# MP_Power_Circuit.net
KiCad netlist of a schematic drawn in Altium Designer
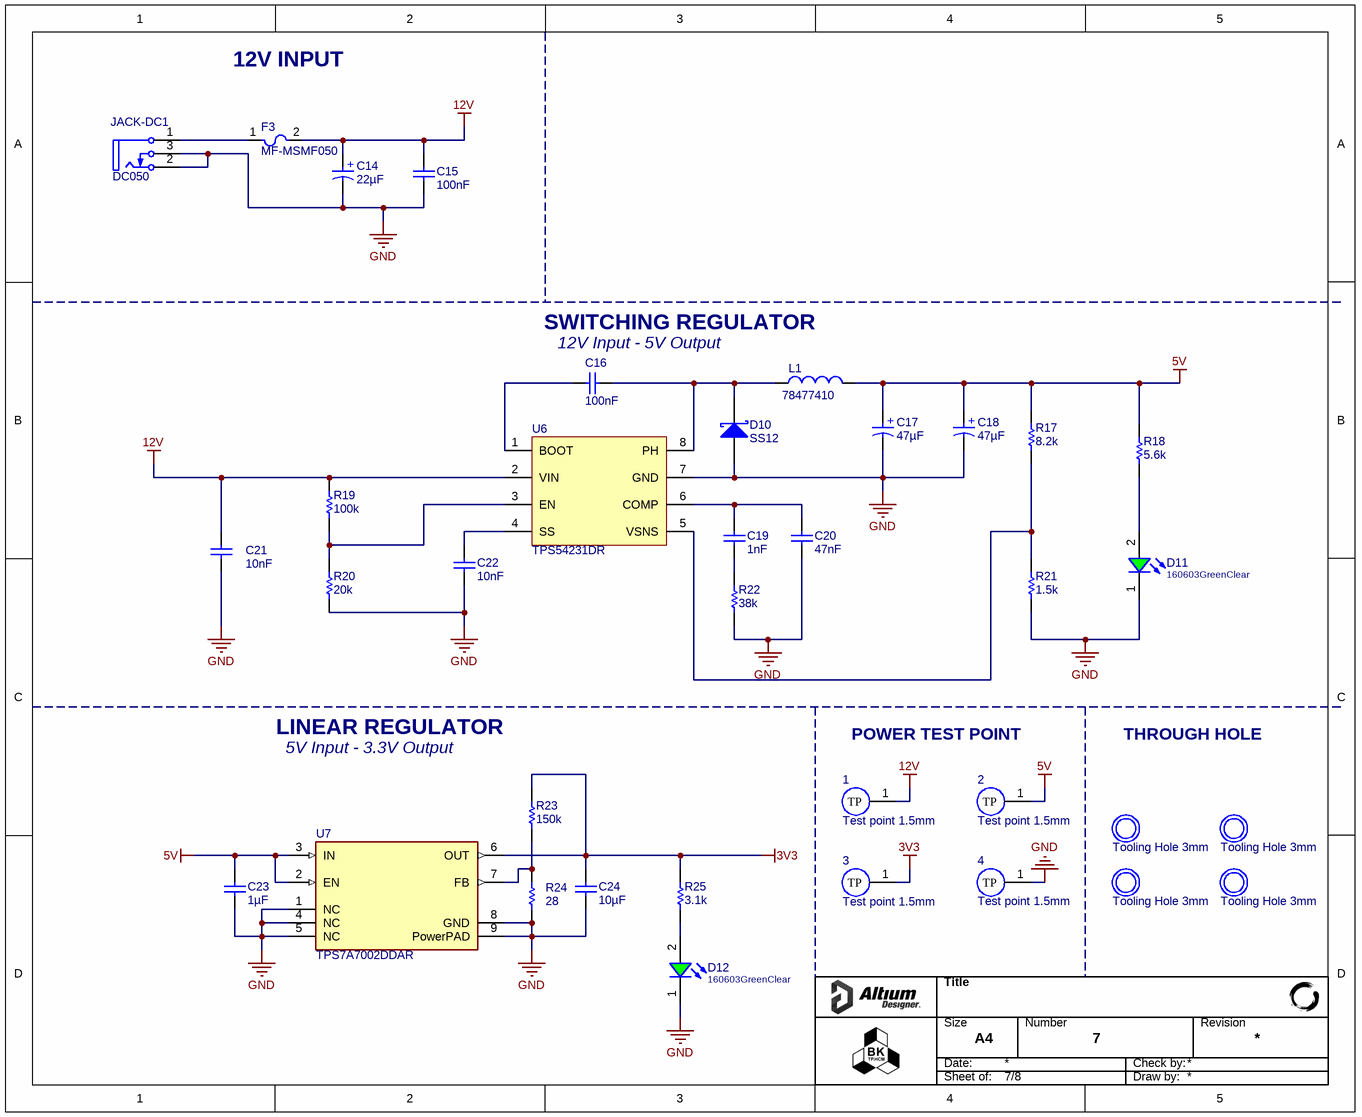
[diagram p0: [MP] Power Circuit.SchDoc]

(export (version "E")
  (design (tool "Eeschema 10.0.6"))
  (components
    (comp (ref "1")
      (value "Test point 1.5mm")
      (footprint "Test point 1.5mm-Footprint-1")
      (description "Test point, 1.5mm radius")
      (libsource (lib "University of Technology") (part "TP"))
    )
    (comp (ref "2")
      (value "Test point 1.5mm")
      (footprint "Test point 1.5mm-Footprint-1")
      (description "Test point, 1.5mm radius")
      (libsource (lib "University of Technology") (part "TP"))
    )
    (comp (ref "3")
      (value "Test point 1.5mm")
      (footprint "Test point 1.5mm-Footprint-1")
      (description "Test point, 1.5mm radius")
      (libsource (lib "University of Technology") (part "TP"))
    )
    (comp (ref "4")
      (value "Test point 1.5mm")
      (footprint "Test point 1.5mm-Footprint-1")
      (description "Test point, 1.5mm radius")
      (libsource (lib "University of Technology") (part "TP"))
    )
    (comp (ref "C14")
      (value "22µF")
      (footprint "WCAP-ASLI_D4H5.5")
      (description "V-Chip, D4 x H5.5mm, 22uF, 16V")
      (fields (field (name "MANUFACTURER") "Wurth Elektronik") (field (name "Comment") "865080340003"))
      (libsource (lib "University of Technology") (part "0710101508650801570160U20"))
    )
    (comp (ref "C15")
      (value "100nF")
      (footprint "CAP_0603")
      (description "CAP, size 0603, 100 nF, 50 VDC, 10%")
      (fields
        (field (name "TOLERANCE") "10%")
        (field (name "MANUFACTURER PART NUMBER") "CGA3E3X8R1H104K080AE")
        (field (name "SOURCE") "Capacitor_0603_10_percent.SchLib")
      )
      (libsource (lib "University of Technology") (part "010603475106.3"))
    )
    (comp (ref "C16")
      (value "100nF")
      (footprint "CAP_0603")
      (description "CAP, size 0603, 100 nF, 50 VDC, 10%")
      (fields
        (field (name "TOLERANCE") "10%")
        (field (name "MANUFACTURER PART NUMBER") "CGA3E3X8R1H104K080AE")
        (field (name "SOURCE") "Capacitor_0603_10_percent.SchLib")
      )
      (libsource (lib "University of Technology") (part "010603475106.3"))
    )
    (comp (ref "C17")
      (value "47µF")
      (footprint "WCAP-ASLI_D5H5.5")
      (description "V-Chip, D5 x H5.5mm, 47uF, 16V")
      (fields (field (name "MANUFACTURER") "Wurth Elektronik") (field (name "Comment") "865080342006"))
      (libsource (lib "University of Technology") (part "0710101508650801570160U20"))
    )
    (comp (ref "C18")
      (value "47µF")
      (footprint "WCAP-ASLI_D5H5.5")
      (description "V-Chip, D5 x H5.5mm, 47uF, 16V")
      (fields (field (name "MANUFACTURER") "Wurth Elektronik") (field (name "Comment") "865080342006"))
      (libsource (lib "University of Technology") (part "0710101508650801570160U20"))
    )
    (comp (ref "C19")
      (value "1nF")
      (footprint "CAP_0603")
      (description "CAP, size 0603, 1 nF, 50 VDC, 5%")
      (fields
        (field (name "MANUFACTURER") "TDK")
        (field (name "MANUFACTURER PART NUMBER") "CGA3E2NP01H102J080AA")
        (field (name "SOURCE") "Capacitor_0603_5_percent.SchLib")
      )
      (libsource (lib "University of Technology") (part "0106036820550"))
    )
    (comp (ref "C20")
      (value "47nF")
      (footprint "CAP_0603")
      (description "CAP, size 0603, 47 nF, 50 VDC, 10%")
      (fields
        (field (name "MANUFACTURER PART NUMBER") "CGA3E2X7R1H473K080AA")
        (field (name "MANUFACTURER") "TDK")
        (field (name "SOURCE") "Capacitor_0603_10_percent.SchLib")
      )
      (libsource (lib "University of Technology") (part "010603475106.3"))
    )
    (comp (ref "C21")
      (value "10nF")
      (footprint "CAP_0603")
      (description "CAP, size 0603, 10 nF, 50 VDC, 5%")
      (fields
        (field (name "TOLERANCE") "5%")
        (field (name "MANUFACTURER") "TDK")
        (field (name "SOURCE") "Capacitor_0603_5_percent.SchLib")
      )
      (libsource (lib "University of Technology") (part "0106036820550"))
    )
    (comp (ref "C22")
      (value "10nF")
      (footprint "CAP_0603")
      (description "CAP, size 0603, 10 nF, 50 VDC, 5%")
      (fields
        (field (name "TOLERANCE") "5%")
        (field (name "MANUFACTURER") "TDK")
        (field (name "SOURCE") "Capacitor_0603_5_percent.SchLib")
      )
      (libsource (lib "University of Technology") (part "0106036820550"))
    )
    (comp (ref "C23")
      (value "1µF")
      (footprint "CAP_0603")
      (description "CAP, size 0603, 1 uF, 25 VDC, 10%")
      (fields
        (field (name "MANUFACTURER") "Samsung Electro-Mechanics")
        (field (name "MANUFACTURER PART NUMBER") "CL10A105KA8NNNC")
        (field (name "SOURCE") "Capacitor_0603_10_percent.SchLib")
      )
      (libsource (lib "University of Technology") (part "010603475106.3"))
    )
    (comp (ref "C24")
      (value "10µF")
      (footprint "CAP_0603")
      (description "CAP, size 0603, 10 uF, 10 VDC, 10%")
      (fields
        (field (name "MANUFACTURER") "Samsung Electro-Mechanics")
        (field (name "LCSC PART #") "C19702")
        (field (name "SOURCE") "Capacitor_0603_10_percent.SchLib")
      )
      (libsource (lib "University of Technology") (part "010603475106.3"))
    )
    (comp (ref "D10")
      (value "SS12")
      (footprint "FAIR-DO-214AC-2_V")
      (description "Schottky Rectifier, 20 V, 1 A, -65 to 125 degC, 2-Pin DO-214AC, RoHS, Tape and Reel")
      (fields (field (name "MANUFACTURER") "Fairchild"))
      (libsource (lib "University of Technology") (part "DSKY-AK-2"))
    )
    (comp (ref "D11")
      (value "160603GreenClear")
      (footprint "WL-SMCW_0603_H=0.7mm")
      (description "WL-SMCW SMT Mono-color Chip LED Waterclear, size 0603, Green, 3.2V, 140deg")
      (libsource (lib "University of Technology") (part "160603GreenClear"))
    )
    (comp (ref "D12")
      (value "160603GreenClear")
      (footprint "WL-SMCW_0603_H=0.7mm")
      (description "WL-SMCW SMT Mono-color Chip LED Waterclear, size 0603, Green, 3.2V, 140deg")
      (libsource (lib "University of Technology") (part "160603GreenClear"))
    )
    (comp (ref "F3")
      (value "MF-MSMF050")
      (footprint "BOUR-MF-MSMF050-2_V")
      (description "PTC Resettable Fuse, 15 V, 500 mA, -40 to 85 degC, 2-Pin SMD, RoHS, Tape and Reel")
      (fields (field (name "MANUFACTURER") "Bourns"))
      (libsource (lib "University of Technology") (part "FUSE-2"))
    )
    (comp (ref "H1")
      (value "Tooling Hole 3mm")
      (footprint "3mm")
      (libsource (lib "University of Technology") (part "Tooling Hole 5mm"))
    )
    (comp (ref "H2")
      (value "Tooling Hole 3mm")
      (footprint "3mm")
      (libsource (lib "University of Technology") (part "Tooling Hole 5mm"))
    )
    (comp (ref "H3")
      (value "Tooling Hole 3mm")
      (footprint "3mm")
      (libsource (lib "University of Technology") (part "Tooling Hole 5mm"))
    )
    (comp (ref "H4")
      (value "Tooling Hole 3mm")
      (footprint "3mm")
      (libsource (lib "University of Technology") (part "Tooling Hole 5mm"))
    )
    (comp (ref "JACK-DC1")
      (value "DC050")
      (footprint "DC050-Footprint-1")
      (description "DinxDout 2.1mm-55mm Jack Power DC Receptacle")
      (libsource (lib "University of Technology") (part "J?"))
    )
    (comp (ref "L1")
      (value "78477410")
      (footprint "WE-PD2A_5848")
      (description "General Purpose Inductor")
      (libsource (lib "University of Technology") (part "IND-2_1"))
    )
    (comp (ref "R17")
      (value "8.2k")
      (footprint "0006038251")
      (description "RES, size 0603, 8.2 KOhm, 1/10 W, 1%")
      (fields (field (name "Comment") "0006038251"))
      (libsource (lib "University of Technology") (part "0006038251"))
    )
    (comp (ref "R18")
      (value "5.6k")
      (footprint "RES_0603")
      (description "RES, size 0603, 5.6 KOhm, 1/10 W, 1%")
      (fields (field (name "MANUFACTURER PART NUMBER") "OEM") (field (name "TOLERANCE") "1%"))
      (libsource (lib "University of Technology") (part "00060371541"))
    )
    (comp (ref "R19")
      (value "100k")
      (footprint "RES_0603")
      (description "RES, size 0603, 100 KOhm, 1/10 W, 1%")
      (fields (field (name "MANUFACTURER PART NUMBER") "OEM") (field (name "TOLERANCE") "1%"))
      (libsource (lib "University of Technology") (part "00060371541"))
    )
    (comp (ref "R20")
      (value "20k")
      (footprint "RES_0603")
      (description "RES, size 0603, 20 KOhm, 1/10 W, 1%")
      (fields (field (name "TOLERANCE") "1%") (field (name "LCSC PART #") "C105575"))
      (libsource (lib "University of Technology") (part "00060371541"))
    )
    (comp (ref "R21")
      (value "1.5k")
      (footprint "RES_0603")
      (description "RES, size 0603, 1.5 KOhm, 1/10 W, 1%")
      (fields (field (name "TOLERANCE") "1%") (field (name "MANUFACTURER") "OEM"))
      (libsource (lib "University of Technology") (part "00060371541"))
    )
    (comp (ref "R22")
      (value "38k")
      (footprint "RES_0603")
      (description "RES, size 0603, 38 KOhm, 1/10 W, 5%")
      (fields (field (name "MANUFACTURER") "OEM") (field (name "TOLERANCE") "5%"))
      (libsource (lib "University of Technology") (part "00060371541"))
    )
    (comp (ref "R23")
      (value "150k")
      (footprint "RES_0603")
      (description "RES, size 0603, 150 KOhm, 1/10 W, 1%")
      (fields (field (name "TOLERANCE") "1%") (field (name "MANUFACTURER PART NUMBER") "OEM"))
      (libsource (lib "University of Technology") (part "00060371541"))
    )
    (comp (ref "R24")
      (value "28")
      (footprint "RES_0603")
      (description "RES, size 0603, 28 Ohm, 1/10 W, 1%")
      (fields (field (name "MANUFACTURER") "OEM") (field (name "TOLERANCE") "1%"))
      (libsource (lib "University of Technology") (part "00060371541"))
    )
    (comp (ref "R25")
      (value "3.1k")
      (footprint "RES_0603")
      (description "RES, size 0603, 3.1  KOhm, 1/10 W, 1%")
      (fields (field (name "MANUFACTURER") "OEM") (field (name "TOLERANCE") "1%"))
      (libsource (lib "University of Technology") (part "00060371541"))
    )
    (comp (ref "U6")
      (value "TPS54231DR")
      (footprint "D0008A_L")
      (description "Switching Regulator, Current-mode, 2A, 570kHz Switching Freq-Max, PDSO8")
      (libsource (lib "University of Technology") (part "TI-TPS54231D8"))
    )
    (comp (ref "U7")
      (value "TPS7A7002DDAR")
      (footprint "FP-DDA0008E-IPC_A")
      (description "Adjustable Positive LDO Regulator, 0.5V Min, 5V Max, 0.6V Dropout, CMOS, PDSO8")
      (libsource (lib "University of Technology") (part "faebeb2d6e46d862d344f00b777028a"))
    )
  )
  (nets
    (net (code "1") (name "3V3") (class "Default")
      (node (ref "3") (pin "1") (pinfunction "TP_1") (pintype "passive"))
      (node (ref "C24") (pin "2") (pinfunction "2_2") (pintype "passive"))
      (node (ref "R23") (pin "2") (pinfunction "2_2") (pintype "passive"))
      (node (ref "R25") (pin "2") (pinfunction "2_2") (pintype "passive"))
      (node (ref "U7") (pin "6") (pinfunction "OUT_6") (pintype "output"))
    )
    (net (code "2") (name "5V") (class "Default")
      (node (ref "2") (pin "1") (pinfunction "TP_1") (pintype "passive"))
      (node (ref "C17") (pin "1") (pinfunction "P_1") (pintype "passive"))
      (node (ref "C18") (pin "1") (pinfunction "P_1") (pintype "passive"))
      (node (ref "C23") (pin "2") (pinfunction "2_2") (pintype "passive"))
      (node (ref "L1") (pin "2") (pinfunction "2_2") (pintype "passive"))
      (node (ref "R17") (pin "2") (pinfunction "2_2") (pintype "passive"))
      (node (ref "R18") (pin "2") (pinfunction "2_2") (pintype "passive"))
      (node (ref "U7") (pin "2") (pinfunction "EN_2") (pintype "input"))
      (node (ref "U7") (pin "3") (pinfunction "IN_3") (pintype "input"))
    )
    (net (code "3") (name "12V") (class "Default")
      (node (ref "1") (pin "1") (pinfunction "TP_1") (pintype "passive"))
      (node (ref "C14") (pin "1") (pinfunction "P_1") (pintype "passive"))
      (node (ref "C15") (pin "1") (pinfunction "1_1") (pintype "passive"))
      (node (ref "C21") (pin "2") (pinfunction "2_2") (pintype "passive"))
      (node (ref "F3") (pin "2") (pinfunction "2_2") (pintype "passive"))
      (node (ref "R19") (pin "2") (pinfunction "2_2") (pintype "passive"))
      (node (ref "U6") (pin "2") (pinfunction "VIN_2") (pintype "passive"))
    )
    (net (code "4") (name "GND") (class "Default")
      (node (ref "4") (pin "1") (pinfunction "TP_1") (pintype "passive"))
      (node (ref "C14") (pin "2") (pinfunction "N_2") (pintype "passive"))
      (node (ref "C15") (pin "2") (pinfunction "2_2") (pintype "passive"))
      (node (ref "C17") (pin "2") (pinfunction "N_2") (pintype "passive"))
      (node (ref "C18") (pin "2") (pinfunction "N_2") (pintype "passive"))
      (node (ref "C20") (pin "1") (pinfunction "1_1") (pintype "passive"))
      (node (ref "C21") (pin "1") (pinfunction "1_1") (pintype "passive"))
      (node (ref "C22") (pin "1") (pinfunction "1_1") (pintype "passive"))
      (node (ref "C23") (pin "1") (pinfunction "1_1") (pintype "passive"))
      (node (ref "C24") (pin "1") (pinfunction "1_1") (pintype "passive"))
      (node (ref "D10") (pin "1") (pinfunction "A_1") (pintype "passive"))
      (node (ref "D11") (pin "1") (pinfunction "K_1") (pintype "passive"))
      (node (ref "D12") (pin "1") (pinfunction "K_1") (pintype "passive"))
      (node (ref "JACK-DC1") (pin "2") (pinfunction "TIP_2") (pintype "passive"))
      (node (ref "JACK-DC1") (pin "3") (pinfunction "SHUNT_3") (pintype "passive"))
      (node (ref "R20") (pin "1") (pinfunction "1_1") (pintype "passive"))
      (node (ref "R21") (pin "1") (pinfunction "1_1") (pintype "passive"))
      (node (ref "R22") (pin "1") (pinfunction "1_1") (pintype "passive"))
      (node (ref "R24") (pin "1") (pinfunction "1_1") (pintype "passive"))
      (node (ref "U6") (pin "7") (pinfunction "GND_7") (pintype "passive"))
      (node (ref "U7") (pin "1") (pinfunction "NC_1") (pintype "passive"))
      (node (ref "U7") (pin "4") (pinfunction "NC_4") (pintype "passive"))
      (node (ref "U7") (pin "5") (pinfunction "NC_5") (pintype "passive"))
      (node (ref "U7") (pin "8") (pinfunction "GND_8") (pintype "power_in"))
      (node (ref "U7") (pin "9") (pinfunction "PowerPAD_9") (pintype "power_in"))
    )
    (net (code "5") (name "Net-(C19-Pad1)") (class "Default")
      (node (ref "C19") (pin "1") (pinfunction "1_1") (pintype "passive"))
      (node (ref "R22") (pin "2") (pinfunction "2_2") (pintype "passive"))
    )
    (net (code "6") (name "Net-(D10-K)") (class "Default")
      (node (ref "C16") (pin "2") (pinfunction "2_2") (pintype "passive"))
      (node (ref "D10") (pin "2") (pinfunction "K_2") (pintype "passive"))
      (node (ref "L1") (pin "1") (pinfunction "1_1") (pintype "passive"))
      (node (ref "U6") (pin "8") (pinfunction "PH_8") (pintype "passive"))
    )
    (net (code "7") (name "Net-(D11-A)") (class "Default")
      (node (ref "D11") (pin "2") (pinfunction "A_2") (pintype "passive"))
      (node (ref "R18") (pin "1") (pinfunction "1_1") (pintype "passive"))
    )
    (net (code "8") (name "Net-(D12-A)") (class "Default")
      (node (ref "D12") (pin "2") (pinfunction "A_2") (pintype "passive"))
      (node (ref "R25") (pin "1") (pinfunction "1_1") (pintype "passive"))
    )
    (net (code "9") (name "Net-(JACK-DC1-SLEEVE)") (class "Default")
      (node (ref "F3") (pin "1") (pinfunction "1_1") (pintype "passive"))
      (node (ref "JACK-DC1") (pin "1") (pinfunction "SLEEVE_1") (pintype "passive"))
    )
    (net (code "10") (name "Net-(U6-BOOT)") (class "Default")
      (node (ref "C16") (pin "1") (pinfunction "1_1") (pintype "passive"))
      (node (ref "U6") (pin "1") (pinfunction "BOOT_1") (pintype "passive"))
    )
    (net (code "11") (name "Net-(U6-COMP)") (class "Default")
      (node (ref "C19") (pin "2") (pinfunction "2_2") (pintype "passive"))
      (node (ref "C20") (pin "2") (pinfunction "2_2") (pintype "passive"))
      (node (ref "U6") (pin "6") (pinfunction "COMP_6") (pintype "passive"))
    )
    (net (code "12") (name "Net-(U6-EN)") (class "Default")
      (node (ref "R19") (pin "1") (pinfunction "1_1") (pintype "passive"))
      (node (ref "R20") (pin "2") (pinfunction "2_2") (pintype "passive"))
      (node (ref "U6") (pin "3") (pinfunction "EN_3") (pintype "passive"))
    )
    (net (code "13") (name "Net-(U6-SS)") (class "Default")
      (node (ref "C22") (pin "2") (pinfunction "2_2") (pintype "passive"))
      (node (ref "U6") (pin "4") (pinfunction "SS_4") (pintype "passive"))
    )
    (net (code "14") (name "Net-(U6-VSNS)") (class "Default")
      (node (ref "R17") (pin "1") (pinfunction "1_1") (pintype "passive"))
      (node (ref "R21") (pin "2") (pinfunction "2_2") (pintype "passive"))
      (node (ref "U6") (pin "5") (pinfunction "VSNS_5") (pintype "passive"))
    )
    (net (code "15") (name "Net-(U7-FB)") (class "Default")
      (node (ref "R23") (pin "1") (pinfunction "1_1") (pintype "passive"))
      (node (ref "R24") (pin "2") (pinfunction "2_2") (pintype "passive"))
      (node (ref "U7") (pin "7") (pinfunction "FB_7") (pintype "output"))
    )
  )
)
